# STM32-ROMI_Rev_A_3_OLED_Sensor.net
KiCad netlist of a schematic drawn in Altium Designer
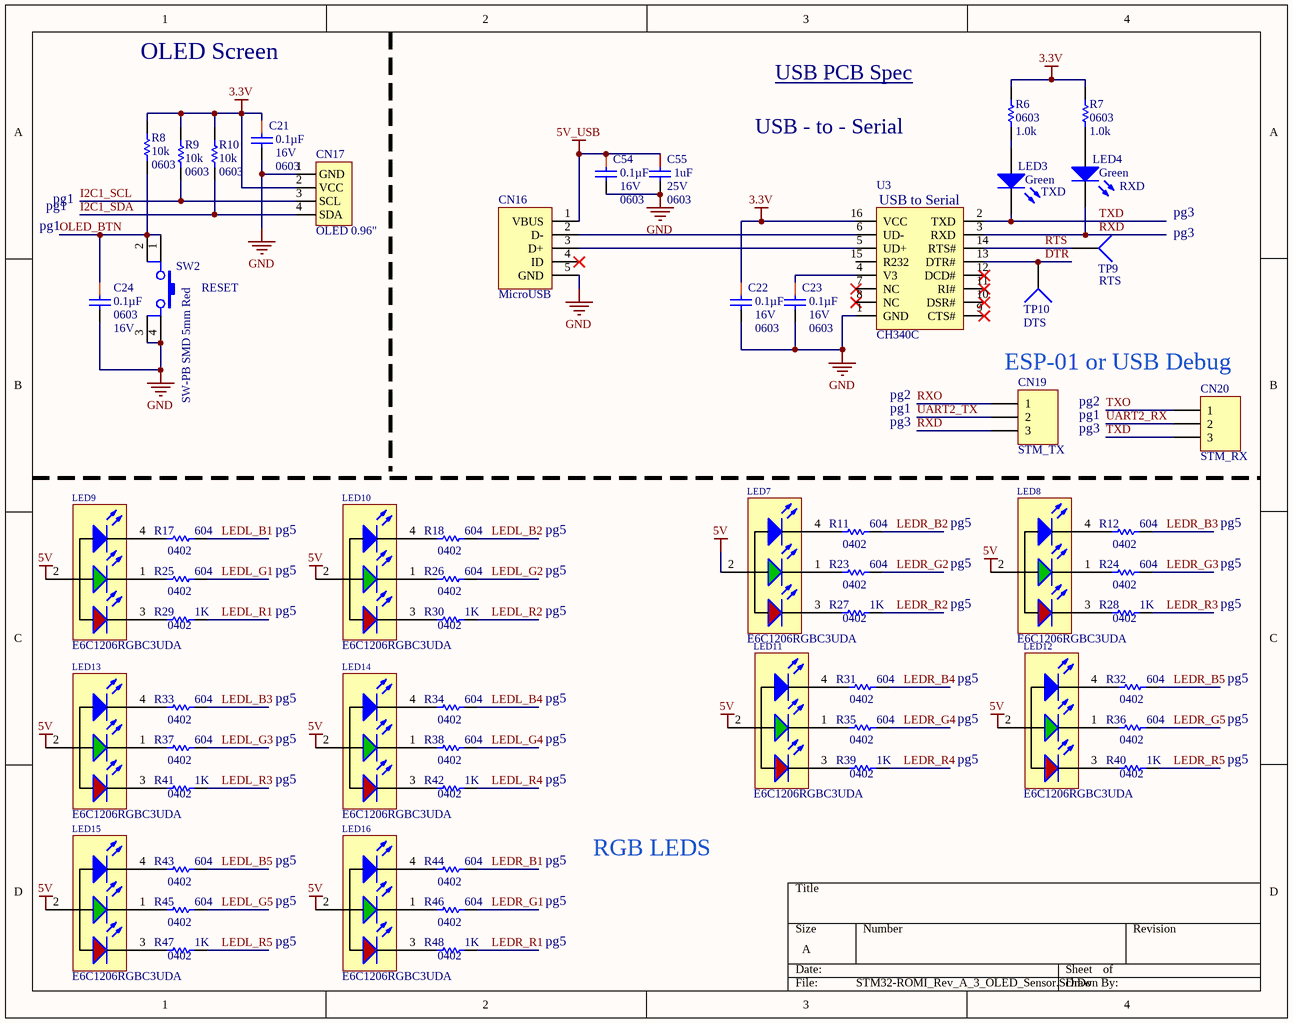
[diagram p0: STM32-ROMI_Rev_A_3_OLED_Sensor.SchDoc]

(export (version "E")
  (design (tool "Eeschema 10.0.6"))
  (components
    (comp (ref "C21")
      (value "0.1uF")
      (footprint "CAPC0603(1608)_L")
      (description "0.1uF 0603 16V")
      (fields
        (field (name "MANUFACTURER") "Kemet")
        (field (name "MANUFACTURER PART NUMBER") "C0603C104K4RACTU")
        (field (name "CAPACITANCE") "0.1µF")
        (field (name "PACKAGE / CASE") "0603")
        (field (name "VOLTAGE - RATED") "16V")
      )
      (libsource (lib "Kyle-Passive") (part "CAP CER 0.1UF 16V 10% X7R 0603"))
    )
    (comp (ref "C22")
      (value "0.1uF")
      (footprint "CAPC0603(1608)_L")
      (description "0.1uF 0603 16V")
      (fields
        (field (name "MANUFACTURER") "Kemet")
        (field (name "MANUFACTURER PART NUMBER") "C0603C104K4RACTU")
        (field (name "CAPACITANCE") "0.1µF")
        (field (name "PACKAGE / CASE") "0603")
        (field (name "VOLTAGE - RATED") "16V")
      )
      (libsource (lib "Kyle-Passive") (part "CAP CER 0.1UF 16V 10% X7R 0603"))
    )
    (comp (ref "C23")
      (value "0.1uF")
      (footprint "CAPC0603(1608)_L")
      (description "0.1uF 0603 16V")
      (fields
        (field (name "MANUFACTURER") "Kemet")
        (field (name "MANUFACTURER PART NUMBER") "C0603C104K4RACTU")
        (field (name "CAPACITANCE") "0.1µF")
        (field (name "PACKAGE / CASE") "0603")
        (field (name "VOLTAGE - RATED") "16V")
      )
      (libsource (lib "Kyle-Passive") (part "CAP CER 0.1UF 16V 10% X7R 0603"))
    )
    (comp (ref "C24")
      (value "0.1uF")
      (footprint "CAPC0603(1608)_L")
      (description "0.1uF 0603 16V")
      (fields
        (field (name "MANUFACTURER") "Kemet")
        (field (name "MANUFACTURER PART NUMBER") "C0603C104K4RACTU")
        (field (name "CAPACITANCE") "0.1µF")
        (field (name "PACKAGE / CASE") "0603")
        (field (name "VOLTAGE - RATED") "16V")
      )
      (libsource (lib "JLCPCB_Passives") (part "CAP CER 0.1UF 16V 10% X7R 0603"))
    )
    (comp (ref "C54")
      (value "0.1uF")
      (footprint "CAPC0603(1608)_L")
      (description "0.1uF 0603 16V")
      (fields
        (field (name "MANUFACTURER") "Kemet")
        (field (name "MANUFACTURER PART NUMBER") "C0603C104K4RACTU")
        (field (name "CAPACITANCE") "0.1µF")
        (field (name "PACKAGE / CASE") "0603")
        (field (name "VOLTAGE - RATED") "16V")
      )
      (libsource (lib "Kyle-Passive") (part "CAP CER 0.1UF 16V 10% X7R 0603"))
    )
    (comp (ref "C55")
      (value "1uF")
      (footprint "CAPC0603(1608)_N")
      (description "1uF 0603 25V")
      (fields
        (field (name "MANUFACTURER") "TDK Corporation")
        (field (name "MANUFACTURER PART NUMBER") "CGA3E1X7R1E105K080AC")
        (field (name "VOLTAGE - RATED") "25V")
        (field (name "PACKAGE / CASE") "0603")
      )
      (libsource (lib "OLogic-Passive") (part "CAP CER 1UF 25V 10% X7R 0603"))
    )
    (comp (ref "CN16")
      (value "MicroUSB")
      (footprint "10118194-0001LF")
      (description "Amphenol FCI CONN USB MICRO B RECPT SMT R/A")
      (fields
        (field (name "MANUFACTURER") "Amphenol FCI")
        (field (name "MANUFACTURER PART NUMBER") "10118194-0001LF")
      )
      (libsource (lib "OLogic-Connectors") (part "10118194-0001LF"))
    )
    (comp (ref "CN17")
      (value "OLED 0.96\"")
      (footprint "OLED_0.96_I2C")
      (description "SSD1306 I2C OLED 0.96\"")
      (libsource (lib "Kyle_Lib_04-20-19") (part "OLED_0.96_I2C"))
    )
    (comp (ref "CN19")
      (value "STM_TX")
      (footprint "HDR1X3")
      (description "Header, 3-Pin")
      (fields
        (field (name "MANUFACTURER") "Sullins Connector Solutions")
        (field (name "MANUFACTURER PART NUMBER") "PRPC003SAAN-RC")
      )
      (libsource (lib "Kyle-Connectors") (part "Header 3"))
    )
    (comp (ref "CN20")
      (value "STM_RX")
      (footprint "HDR1X3")
      (description "Header, 3-Pin")
      (fields
        (field (name "MANUFACTURER") "Sullins Connector Solutions")
        (field (name "MANUFACTURER PART NUMBER") "PRPC003SAAN-RC")
      )
      (libsource (lib "Kyle-Connectors") (part "Header 3"))
    )
    (comp (ref "LED3")
      (value "TXD")
      (footprint "SM-LED-0603")
      (description "LED GREEN CLEAR THIN 0603 SMD")
      (fields
        (field (name "MANUFACTURER") "Lite-On Inc")
        (field (name "MANUFACTURER PART NUMBER") "LTST-C191KGKT")
        (field (name "COLOR") "Green")
      )
      (libsource (lib "Kyle-Diode-Opto-LED") (part "LTST-C191KGKT"))
    )
    (comp (ref "LED4")
      (value "RXD")
      (footprint "SM-LED-0603")
      (description "LED GREEN CLEAR THIN 0603 SMD")
      (fields
        (field (name "MANUFACTURER") "Lite-On Inc")
        (field (name "MANUFACTURER PART NUMBER") "LTST-C191KGKT")
        (field (name "COLOR") "Green")
      )
      (libsource (lib "Kyle-Diode-Opto-LED") (part "LTST-C191KGKT"))
    )
    (comp (ref "LED7")
      (value "E6C1206RGBC3UDA")
      (footprint "E6C1206RGBC3UDA")
      (description "RGB 620NMRED, 520NMGREEN, 465NMBLUE SMD,")
      (libsource (lib "JLCPCB-LED-Diodes") (part "RGB LED"))
    )
    (comp (ref "LED8")
      (value "E6C1206RGBC3UDA")
      (footprint "E6C1206RGBC3UDA")
      (description "RGB 620NMRED, 520NMGREEN, 465NMBLUE SMD,")
      (libsource (lib "JLCPCB-LED-Diodes") (part "RGB LED"))
    )
    (comp (ref "LED9")
      (value "E6C1206RGBC3UDA")
      (footprint "E6C1206RGBC3UDA")
      (description "RGB 620NMRED, 520NMGREEN, 465NMBLUE SMD,")
      (libsource (lib "JLCPCB-LED-Diodes") (part "RGB LED"))
    )
    (comp (ref "LED10")
      (value "E6C1206RGBC3UDA")
      (footprint "E6C1206RGBC3UDA")
      (description "RGB 620NMRED, 520NMGREEN, 465NMBLUE SMD,")
      (libsource (lib "JLCPCB-LED-Diodes") (part "RGB LED"))
    )
    (comp (ref "LED11")
      (value "E6C1206RGBC3UDA")
      (footprint "E6C1206RGBC3UDA")
      (description "RGB 620NMRED, 520NMGREEN, 465NMBLUE SMD,")
      (libsource (lib "JLCPCB-LED-Diodes") (part "RGB LED"))
    )
    (comp (ref "LED12")
      (value "E6C1206RGBC3UDA")
      (footprint "E6C1206RGBC3UDA")
      (description "RGB 620NMRED, 520NMGREEN, 465NMBLUE SMD,")
      (libsource (lib "JLCPCB-LED-Diodes") (part "RGB LED"))
    )
    (comp (ref "LED13")
      (value "E6C1206RGBC3UDA")
      (footprint "E6C1206RGBC3UDA")
      (description "RGB 620NMRED, 520NMGREEN, 465NMBLUE SMD,")
      (libsource (lib "JLCPCB-LED-Diodes") (part "RGB LED"))
    )
    (comp (ref "LED14")
      (value "E6C1206RGBC3UDA")
      (footprint "E6C1206RGBC3UDA")
      (description "RGB 620NMRED, 520NMGREEN, 465NMBLUE SMD,")
      (libsource (lib "JLCPCB-LED-Diodes") (part "RGB LED"))
    )
    (comp (ref "LED15")
      (value "E6C1206RGBC3UDA")
      (footprint "E6C1206RGBC3UDA")
      (description "RGB 620NMRED, 520NMGREEN, 465NMBLUE SMD,")
      (libsource (lib "JLCPCB-LED-Diodes") (part "RGB LED"))
    )
    (comp (ref "LED16")
      (value "E6C1206RGBC3UDA")
      (footprint "E6C1206RGBC3UDA")
      (description "RGB 620NMRED, 520NMGREEN, 465NMBLUE SMD,")
      (libsource (lib "JLCPCB-LED-Diodes") (part "RGB LED"))
    )
    (comp (ref "R6")
      (value "1.0K")
      (footprint "RESC0603(1608)_N")
      (description "1.0K 0603")
      (fields
        (field (name "MANUFACTURER") "Stackpole Electronics Inc.")
        (field (name "MANUFACTURER PART NUMBER") "RMCF0603FT1K00")
        (field (name "PACKAGE / CASE") "0603")
        (field (name "RESISTANCE (OHMS)") "1.0k")
      )
      (libsource (lib "Kyle-Passive") (part "RES 1K OHM 1% 1/10W 0603"))
    )
    (comp (ref "R7")
      (value "1.0K")
      (footprint "RESC0603(1608)_N")
      (description "1.0K 0603")
      (fields
        (field (name "MANUFACTURER") "Stackpole Electronics Inc.")
        (field (name "MANUFACTURER PART NUMBER") "RMCF0603FT1K00")
        (field (name "PACKAGE / CASE") "0603")
        (field (name "RESISTANCE (OHMS)") "1.0k")
      )
      (libsource (lib "Kyle-Passive") (part "RES 1K OHM 1% 1/10W 0603"))
    )
    (comp (ref "R8")
      (value "10K 1%")
      (footprint "RESC0603(1608)_L")
      (description "10K 0603")
      (fields
        (field (name "MANUFACTURER") "Panasonic Electronic Components")
        (field (name "MANUFACTURER PART NUMBER") "ERJ-3EKF1002V")
        (field (name "RESISTANCE (OHMS)") "10k")
        (field (name "PACKAGE / CASE") "0603")
      )
      (libsource (lib "Kyle-Passive") (part "RES 10K OHM 1/10W 1% 0603 SMD"))
    )
    (comp (ref "R9")
      (value "10K 1%")
      (footprint "RESC0603(1608)_L")
      (description "10K 0603")
      (fields
        (field (name "MANUFACTURER") "Panasonic Electronic Components")
        (field (name "MANUFACTURER PART NUMBER") "ERJ-3EKF1002V")
        (field (name "RESISTANCE (OHMS)") "10k")
        (field (name "PACKAGE / CASE") "0603")
      )
      (libsource (lib "Kyle-Passive") (part "RES 10K OHM 1/10W 1% 0603 SMD"))
    )
    (comp (ref "R10")
      (value "10K 1%")
      (footprint "RESC0603(1608)_L")
      (description "10K 0603")
      (fields
        (field (name "MANUFACTURER") "Panasonic Electronic Components")
        (field (name "MANUFACTURER PART NUMBER") "ERJ-3EKF1002V")
        (field (name "RESISTANCE (OHMS)") "10k")
        (field (name "PACKAGE / CASE") "0603")
      )
      (libsource (lib "Kyle-Passive") (part "RES 10K OHM 1/10W 1% 0603 SMD"))
    )
    (comp (ref "R11")
      (value "604")
      (footprint "RESC0402(1005)_L")
      (description "604 0402")
      (fields
        (field (name "MANUFACTURER") "Panasonic Electronic Components")
        (field (name "MANUFACTURER PART NUMBER") "ERA-2AEB6040X")
        (field (name "SUPPLIER DEVICE PACKAGE") "0402")
      )
      (libsource (lib "OLogic-Passive") (part "RES 604 OHM 1% 1/10W 0402"))
    )
    (comp (ref "R12")
      (value "604")
      (footprint "RESC0402(1005)_L")
      (description "604 0402")
      (fields
        (field (name "MANUFACTURER") "Panasonic Electronic Components")
        (field (name "MANUFACTURER PART NUMBER") "ERA-2AEB6040X")
        (field (name "SUPPLIER DEVICE PACKAGE") "0402")
      )
      (libsource (lib "OLogic-Passive") (part "RES 604 OHM 1% 1/10W 0402"))
    )
    (comp (ref "R17")
      (value "604")
      (footprint "RESC0402(1005)_L")
      (description "604 0402")
      (fields
        (field (name "MANUFACTURER") "Panasonic Electronic Components")
        (field (name "MANUFACTURER PART NUMBER") "ERA-2AEB6040X")
        (field (name "SUPPLIER DEVICE PACKAGE") "0402")
      )
      (libsource (lib "OLogic-Passive") (part "RES 604 OHM 1% 1/10W 0402"))
    )
    (comp (ref "R18")
      (value "604")
      (footprint "RESC0402(1005)_L")
      (description "604 0402")
      (fields
        (field (name "MANUFACTURER") "Panasonic Electronic Components")
        (field (name "MANUFACTURER PART NUMBER") "ERA-2AEB6040X")
        (field (name "SUPPLIER DEVICE PACKAGE") "0402")
      )
      (libsource (lib "OLogic-Passive") (part "RES 604 OHM 1% 1/10W 0402"))
    )
    (comp (ref "R23")
      (value "604")
      (footprint "RESC0402(1005)_L")
      (description "604 0402")
      (fields
        (field (name "MANUFACTURER") "Panasonic Electronic Components")
        (field (name "MANUFACTURER PART NUMBER") "ERA-2AEB6040X")
        (field (name "SUPPLIER DEVICE PACKAGE") "0402")
      )
      (libsource (lib "OLogic-Passive") (part "RES 604 OHM 1% 1/10W 0402"))
    )
    (comp (ref "R24")
      (value "604")
      (footprint "RESC0402(1005)_L")
      (description "604 0402")
      (fields
        (field (name "MANUFACTURER") "Panasonic Electronic Components")
        (field (name "MANUFACTURER PART NUMBER") "ERA-2AEB6040X")
        (field (name "SUPPLIER DEVICE PACKAGE") "0402")
      )
      (libsource (lib "OLogic-Passive") (part "RES 604 OHM 1% 1/10W 0402"))
    )
    (comp (ref "R25")
      (value "604")
      (footprint "RESC0402(1005)_L")
      (description "604 0402")
      (fields
        (field (name "MANUFACTURER") "Panasonic Electronic Components")
        (field (name "MANUFACTURER PART NUMBER") "ERA-2AEB6040X")
        (field (name "SUPPLIER DEVICE PACKAGE") "0402")
      )
      (libsource (lib "OLogic-Passive") (part "RES 604 OHM 1% 1/10W 0402"))
    )
    (comp (ref "R26")
      (value "604")
      (footprint "RESC0402(1005)_L")
      (description "604 0402")
      (fields
        (field (name "MANUFACTURER") "Panasonic Electronic Components")
        (field (name "MANUFACTURER PART NUMBER") "ERA-2AEB6040X")
        (field (name "SUPPLIER DEVICE PACKAGE") "0402")
      )
      (libsource (lib "OLogic-Passive") (part "RES 604 OHM 1% 1/10W 0402"))
    )
    (comp (ref "R27")
      (value "1K")
      (footprint "RESC0402(1005)_L")
      (description "1K 0402")
      (fields
        (field (name "MANUFACTURER") "Yageo")
        (field (name "MANUFACTURER PART NUMBER") "RC0402FR-071KL")
        (field (name "CASE CODE (IMPERIAL)") "0402")
        (field (name "RESISTANCE") "1K")
      )
      (libsource (lib "OLogic-Passive") (part "RES 1K OHM 1% 1/16W 0402"))
    )
    (comp (ref "R28")
      (value "1K")
      (footprint "RESC0402(1005)_L")
      (description "1K 0402")
      (fields
        (field (name "MANUFACTURER") "Yageo")
        (field (name "MANUFACTURER PART NUMBER") "RC0402FR-071KL")
        (field (name "CASE CODE (IMPERIAL)") "0402")
        (field (name "RESISTANCE") "1K")
      )
      (libsource (lib "OLogic-Passive") (part "RES 1K OHM 1% 1/16W 0402"))
    )
    (comp (ref "R29")
      (value "1K")
      (footprint "RESC0402(1005)_L")
      (description "1K 0402")
      (fields
        (field (name "MANUFACTURER") "Yageo")
        (field (name "MANUFACTURER PART NUMBER") "RC0402FR-071KL")
        (field (name "CASE CODE (IMPERIAL)") "0402")
        (field (name "RESISTANCE") "1K")
      )
      (libsource (lib "OLogic-Passive") (part "RES 1K OHM 1% 1/16W 0402"))
    )
    (comp (ref "R30")
      (value "1K")
      (footprint "RESC0402(1005)_L")
      (description "1K 0402")
      (fields
        (field (name "MANUFACTURER") "Yageo")
        (field (name "MANUFACTURER PART NUMBER") "RC0402FR-071KL")
        (field (name "CASE CODE (IMPERIAL)") "0402")
        (field (name "RESISTANCE") "1K")
      )
      (libsource (lib "OLogic-Passive") (part "RES 1K OHM 1% 1/16W 0402"))
    )
    (comp (ref "R31")
      (value "604")
      (footprint "RESC0402(1005)_L")
      (description "604 0402")
      (fields
        (field (name "MANUFACTURER") "Panasonic Electronic Components")
        (field (name "MANUFACTURER PART NUMBER") "ERA-2AEB6040X")
        (field (name "SUPPLIER DEVICE PACKAGE") "0402")
      )
      (libsource (lib "OLogic-Passive") (part "RES 604 OHM 1% 1/10W 0402"))
    )
    (comp (ref "R32")
      (value "604")
      (footprint "RESC0402(1005)_L")
      (description "604 0402")
      (fields
        (field (name "MANUFACTURER") "Panasonic Electronic Components")
        (field (name "MANUFACTURER PART NUMBER") "ERA-2AEB6040X")
        (field (name "SUPPLIER DEVICE PACKAGE") "0402")
      )
      (libsource (lib "OLogic-Passive") (part "RES 604 OHM 1% 1/10W 0402"))
    )
    (comp (ref "R33")
      (value "604")
      (footprint "RESC0402(1005)_L")
      (description "604 0402")
      (fields
        (field (name "MANUFACTURER") "Panasonic Electronic Components")
        (field (name "MANUFACTURER PART NUMBER") "ERA-2AEB6040X")
        (field (name "SUPPLIER DEVICE PACKAGE") "0402")
      )
      (libsource (lib "OLogic-Passive") (part "RES 604 OHM 1% 1/10W 0402"))
    )
    (comp (ref "R34")
      (value "604")
      (footprint "RESC0402(1005)_L")
      (description "604 0402")
      (fields
        (field (name "MANUFACTURER") "Panasonic Electronic Components")
        (field (name "MANUFACTURER PART NUMBER") "ERA-2AEB6040X")
        (field (name "SUPPLIER DEVICE PACKAGE") "0402")
      )
      (libsource (lib "OLogic-Passive") (part "RES 604 OHM 1% 1/10W 0402"))
    )
    (comp (ref "R35")
      (value "604")
      (footprint "RESC0402(1005)_L")
      (description "604 0402")
      (fields
        (field (name "MANUFACTURER") "Panasonic Electronic Components")
        (field (name "MANUFACTURER PART NUMBER") "ERA-2AEB6040X")
        (field (name "SUPPLIER DEVICE PACKAGE") "0402")
      )
      (libsource (lib "OLogic-Passive") (part "RES 604 OHM 1% 1/10W 0402"))
    )
    (comp (ref "R36")
      (value "604")
      (footprint "RESC0402(1005)_L")
      (description "604 0402")
      (fields
        (field (name "MANUFACTURER") "Panasonic Electronic Components")
        (field (name "MANUFACTURER PART NUMBER") "ERA-2AEB6040X")
        (field (name "SUPPLIER DEVICE PACKAGE") "0402")
      )
      (libsource (lib "OLogic-Passive") (part "RES 604 OHM 1% 1/10W 0402"))
    )
    (comp (ref "R37")
      (value "604")
      (footprint "RESC0402(1005)_L")
      (description "604 0402")
      (fields
        (field (name "MANUFACTURER") "Panasonic Electronic Components")
        (field (name "MANUFACTURER PART NUMBER") "ERA-2AEB6040X")
        (field (name "SUPPLIER DEVICE PACKAGE") "0402")
      )
      (libsource (lib "OLogic-Passive") (part "RES 604 OHM 1% 1/10W 0402"))
    )
    (comp (ref "R38")
      (value "604")
      (footprint "RESC0402(1005)_L")
      (description "604 0402")
      (fields
        (field (name "MANUFACTURER") "Panasonic Electronic Components")
        (field (name "MANUFACTURER PART NUMBER") "ERA-2AEB6040X")
        (field (name "SUPPLIER DEVICE PACKAGE") "0402")
      )
      (libsource (lib "OLogic-Passive") (part "RES 604 OHM 1% 1/10W 0402"))
    )
    (comp (ref "R39")
      (value "1K")
      (footprint "RESC0402(1005)_L")
      (description "1K 0402")
      (fields
        (field (name "MANUFACTURER") "Yageo")
        (field (name "MANUFACTURER PART NUMBER") "RC0402FR-071KL")
        (field (name "CASE CODE (IMPERIAL)") "0402")
        (field (name "RESISTANCE") "1K")
      )
      (libsource (lib "OLogic-Passive") (part "RES 1K OHM 1% 1/16W 0402"))
    )
    (comp (ref "R40")
      (value "1K")
      (footprint "RESC0402(1005)_L")
      (description "1K 0402")
      (fields
        (field (name "MANUFACTURER") "Yageo")
        (field (name "MANUFACTURER PART NUMBER") "RC0402FR-071KL")
        (field (name "CASE CODE (IMPERIAL)") "0402")
        (field (name "RESISTANCE") "1K")
      )
      (libsource (lib "OLogic-Passive") (part "RES 1K OHM 1% 1/16W 0402"))
    )
    (comp (ref "R41")
      (value "1K")
      (footprint "RESC0402(1005)_L")
      (description "1K 0402")
      (fields
        (field (name "MANUFACTURER") "Yageo")
        (field (name "MANUFACTURER PART NUMBER") "RC0402FR-071KL")
        (field (name "CASE CODE (IMPERIAL)") "0402")
        (field (name "RESISTANCE") "1K")
      )
      (libsource (lib "OLogic-Passive") (part "RES 1K OHM 1% 1/16W 0402"))
    )
    (comp (ref "R42")
      (value "1K")
      (footprint "RESC0402(1005)_L")
      (description "1K 0402")
      (fields
        (field (name "MANUFACTURER") "Yageo")
        (field (name "MANUFACTURER PART NUMBER") "RC0402FR-071KL")
        (field (name "CASE CODE (IMPERIAL)") "0402")
        (field (name "RESISTANCE") "1K")
      )
      (libsource (lib "OLogic-Passive") (part "RES 1K OHM 1% 1/16W 0402"))
    )
    (comp (ref "R43")
      (value "604")
      (footprint "RESC0402(1005)_L")
      (description "604 0402")
      (fields
        (field (name "MANUFACTURER") "Panasonic Electronic Components")
        (field (name "MANUFACTURER PART NUMBER") "ERA-2AEB6040X")
        (field (name "SUPPLIER DEVICE PACKAGE") "0402")
      )
      (libsource (lib "OLogic-Passive") (part "RES 604 OHM 1% 1/10W 0402"))
    )
    (comp (ref "R44")
      (value "604")
      (footprint "RESC0402(1005)_L")
      (description "604 0402")
      (fields
        (field (name "MANUFACTURER") "Panasonic Electronic Components")
        (field (name "MANUFACTURER PART NUMBER") "ERA-2AEB6040X")
        (field (name "SUPPLIER DEVICE PACKAGE") "0402")
      )
      (libsource (lib "OLogic-Passive") (part "RES 604 OHM 1% 1/10W 0402"))
    )
    (comp (ref "R45")
      (value "604")
      (footprint "RESC0402(1005)_L")
      (description "604 0402")
      (fields
        (field (name "MANUFACTURER") "Panasonic Electronic Components")
        (field (name "MANUFACTURER PART NUMBER") "ERA-2AEB6040X")
        (field (name "SUPPLIER DEVICE PACKAGE") "0402")
      )
      (libsource (lib "OLogic-Passive") (part "RES 604 OHM 1% 1/10W 0402"))
    )
    (comp (ref "R46")
      (value "604")
      (footprint "RESC0402(1005)_L")
      (description "604 0402")
      (fields
        (field (name "MANUFACTURER") "Panasonic Electronic Components")
        (field (name "MANUFACTURER PART NUMBER") "ERA-2AEB6040X")
        (field (name "SUPPLIER DEVICE PACKAGE") "0402")
      )
      (libsource (lib "OLogic-Passive") (part "RES 604 OHM 1% 1/10W 0402"))
    )
    (comp (ref "R47")
      (value "1K")
      (footprint "RESC0402(1005)_L")
      (description "1K 0402")
      (fields
        (field (name "MANUFACTURER") "Yageo")
        (field (name "MANUFACTURER PART NUMBER") "RC0402FR-071KL")
        (field (name "CASE CODE (IMPERIAL)") "0402")
        (field (name "RESISTANCE") "1K")
      )
      (libsource (lib "OLogic-Passive") (part "RES 1K OHM 1% 1/16W 0402"))
    )
    (comp (ref "R48")
      (value "1K")
      (footprint "RESC0402(1005)_L")
      (description "1K 0402")
      (fields
        (field (name "MANUFACTURER") "Yageo")
        (field (name "MANUFACTURER PART NUMBER") "RC0402FR-071KL")
        (field (name "CASE CODE (IMPERIAL)") "0402")
        (field (name "RESISTANCE") "1K")
      )
      (libsource (lib "OLogic-Passive") (part "RES 1K OHM 1% 1/16W 0402"))
    )
    (comp (ref "SW2")
      (value "RESET")
      (footprint "SW TACT Red 6mm x 6mm")
      (description "SWITCH TACTILE SPST-NO 0.05A 12V")
      (fields
        (field (name "MANUFACTURER") "C&K Components")
        (field (name "MANUFACTURER PART NUMBER") "PTS645SK50SMTR92 LFS")
        (field (name "TEXT") "SW-PB SMD 5mm Red")
        (field (name "PUBLISHER") "Altium Limited")
      )
      (libsource (lib "OLogic-Switches") (part "SW-PB SMD 5mm Red"))
    )
    (comp (ref "TP9")
      (value "RTS")
      (footprint "TestPoint-SM")
      (description "Test Point")
      (libsource (lib "OLogic-Misc") (part "TestPoint"))
    )
    (comp (ref "TP10")
      (value "DTS")
      (footprint "TestPoint-SM")
      (description "Test Point")
      (libsource (lib "OLogic-Misc") (part "TestPoint"))
    )
    (comp (ref "U3")
      (value "CH340C")
      (footprint "SOP-16")
      (description "USB to Serial UART")
      (libsource (lib "Kyle_Lib_04-20-19") (part "CH340C"))
    )
  )
  (nets
    (net (code "1") (name "/DTR") (class "Default")
      (node (ref "TP10") (pin "1") (pinfunction "1_1") (pintype "passive"))
      (node (ref "U3") (pin "13") (pinfunction "DTR#_13") (pintype "power_in"))
    )
    (net (code "2") (name "/I2C1_SCL") (class "Default")
      (node (ref "CN17") (pin "3") (pinfunction "SCL_3") (pintype "passive"))
      (node (ref "R9") (pin "1") (pinfunction "1_1") (pintype "passive"))
    )
    (net (code "3") (name "/I2C1_SDA") (class "Default")
      (node (ref "CN17") (pin "4") (pinfunction "SDA_4") (pintype "passive"))
      (node (ref "R10") (pin "1") (pinfunction "1_1") (pintype "passive"))
    )
    (net (code "4") (name "/LEDL_B1") (class "Default")
      (node (ref "R17") (pin "1") (pinfunction "1_1") (pintype "passive"))
    )
    (net (code "5") (name "/LEDL_B2") (class "Default")
      (node (ref "R18") (pin "1") (pinfunction "1_1") (pintype "passive"))
    )
    (net (code "6") (name "/LEDL_B3") (class "Default")
      (node (ref "R33") (pin "1") (pinfunction "1_1") (pintype "passive"))
    )
    (net (code "7") (name "/LEDL_B4") (class "Default")
      (node (ref "R34") (pin "1") (pinfunction "1_1") (pintype "passive"))
    )
    (net (code "8") (name "/LEDL_B5") (class "Default")
      (node (ref "R43") (pin "1") (pinfunction "1_1") (pintype "passive"))
    )
    (net (code "9") (name "/LEDL_G1") (class "Default")
      (node (ref "R25") (pin "1") (pinfunction "1_1") (pintype "passive"))
    )
    (net (code "10") (name "/LEDL_G2") (class "Default")
      (node (ref "R26") (pin "1") (pinfunction "1_1") (pintype "passive"))
    )
    (net (code "11") (name "/LEDL_G3") (class "Default")
      (node (ref "R37") (pin "1") (pinfunction "1_1") (pintype "passive"))
    )
    (net (code "12") (name "/LEDL_G4") (class "Default")
      (node (ref "R38") (pin "1") (pinfunction "1_1") (pintype "passive"))
    )
    (net (code "13") (name "/LEDL_G5") (class "Default")
      (node (ref "R45") (pin "1") (pinfunction "1_1") (pintype "passive"))
    )
    (net (code "14") (name "/LEDL_R1") (class "Default")
      (node (ref "R29") (pin "1") (pinfunction "1_1") (pintype "passive"))
    )
    (net (code "15") (name "/LEDL_R2") (class "Default")
      (node (ref "R30") (pin "1") (pinfunction "1_1") (pintype "passive"))
    )
    (net (code "16") (name "/LEDL_R3") (class "Default")
      (node (ref "R41") (pin "1") (pinfunction "1_1") (pintype "passive"))
    )
    (net (code "17") (name "/LEDL_R4") (class "Default")
      (node (ref "R42") (pin "1") (pinfunction "1_1") (pintype "passive"))
    )
    (net (code "18") (name "/LEDL_R5") (class "Default")
      (node (ref "R47") (pin "1") (pinfunction "1_1") (pintype "passive"))
    )
    (net (code "19") (name "/LEDR_B1") (class "Default")
      (node (ref "R44") (pin "1") (pinfunction "1_1") (pintype "passive"))
    )
    (net (code "20") (name "/LEDR_B2") (class "Default")
      (node (ref "R11") (pin "1") (pinfunction "1_1") (pintype "passive"))
    )
    (net (code "21") (name "/LEDR_B3") (class "Default")
      (node (ref "R12") (pin "1") (pinfunction "1_1") (pintype "passive"))
    )
    (net (code "22") (name "/LEDR_B4") (class "Default")
      (node (ref "R31") (pin "1") (pinfunction "1_1") (pintype "passive"))
    )
    (net (code "23") (name "/LEDR_B5") (class "Default")
      (node (ref "R32") (pin "1") (pinfunction "1_1") (pintype "passive"))
    )
    (net (code "24") (name "/LEDR_G1") (class "Default")
      (node (ref "R46") (pin "1") (pinfunction "1_1") (pintype "passive"))
    )
    (net (code "25") (name "/LEDR_G2") (class "Default")
      (node (ref "R23") (pin "1") (pinfunction "1_1") (pintype "passive"))
    )
    (net (code "26") (name "/LEDR_G3") (class "Default")
      (node (ref "R24") (pin "1") (pinfunction "1_1") (pintype "passive"))
    )
    (net (code "27") (name "/LEDR_G4") (class "Default")
      (node (ref "R35") (pin "1") (pinfunction "1_1") (pintype "passive"))
    )
    (net (code "28") (name "/LEDR_G5") (class "Default")
      (node (ref "R36") (pin "1") (pinfunction "1_1") (pintype "passive"))
    )
    (net (code "29") (name "/LEDR_R1") (class "Default")
      (node (ref "R48") (pin "1") (pinfunction "1_1") (pintype "passive"))
    )
    (net (code "30") (name "/LEDR_R2") (class "Default")
      (node (ref "R27") (pin "1") (pinfunction "1_1") (pintype "passive"))
    )
    (net (code "31") (name "/LEDR_R3") (class "Default")
      (node (ref "R28") (pin "1") (pinfunction "1_1") (pintype "passive"))
    )
    (net (code "32") (name "/LEDR_R4") (class "Default")
      (node (ref "R39") (pin "1") (pinfunction "1_1") (pintype "passive"))
    )
    (net (code "33") (name "/LEDR_R5") (class "Default")
      (node (ref "R40") (pin "1") (pinfunction "1_1") (pintype "passive"))
    )
    (net (code "34") (name "/OLED_BTN") (class "Default")
      (node (ref "C24") (pin "1") (pinfunction "1_1") (pintype "passive"))
      (node (ref "R8") (pin "1") (pinfunction "1_1") (pintype "passive"))
      (node (ref "SW2") (pin "1") (pinfunction "1_1") (pintype "passive"))
      (node (ref "SW2") (pin "2") (pinfunction "2_2") (pintype "passive"))
    )
    (net (code "35") (name "/RTS") (class "Default")
      (node (ref "TP9") (pin "1") (pinfunction "1_1") (pintype "passive"))
      (node (ref "U3") (pin "14") (pinfunction "RTS#_14") (pintype "power_in"))
    )
    (net (code "36") (name "/RXD") (class "Default")
      (node (ref "CN19") (pin "3") (pinfunction "3_3") (pintype "passive"))
      (node (ref "LED4") (pin "2") (pinfunction "2_2") (pintype "passive"))
      (node (ref "U3") (pin "3") (pinfunction "RXD_3") (pintype "power_in"))
    )
    (net (code "37") (name "/RXO") (class "Default")
      (node (ref "CN19") (pin "1") (pinfunction "1_1") (pintype "passive"))
    )
    (net (code "38") (name "/TXD") (class "Default")
      (node (ref "CN20") (pin "3") (pinfunction "3_3") (pintype "passive"))
      (node (ref "LED3") (pin "2") (pinfunction "2_2") (pintype "passive"))
      (node (ref "U3") (pin "2") (pinfunction "TXD_2") (pintype "power_in"))
    )
    (net (code "39") (name "/TXO") (class "Default")
      (node (ref "CN20") (pin "1") (pinfunction "1_1") (pintype "passive"))
    )
    (net (code "40") (name "/UART2_RX") (class "Default")
      (node (ref "CN20") (pin "2") (pinfunction "2_2") (pintype "passive"))
    )
    (net (code "41") (name "/UART2_TX") (class "Default")
      (node (ref "CN19") (pin "2") (pinfunction "2_2") (pintype "passive"))
    )
    (net (code "42") (name "3.3V") (class "Default")
      (node (ref "C21") (pin "1") (pinfunction "1_1") (pintype "passive"))
      (node (ref "C22") (pin "1") (pinfunction "1_1") (pintype "passive"))
      (node (ref "CN17") (pin "2") (pinfunction "VCC_2") (pintype "passive"))
      (node (ref "R10") (pin "2") (pinfunction "2_2") (pintype "passive"))
      (node (ref "R6") (pin "2") (pinfunction "2_2") (pintype "passive"))
      (node (ref "R7") (pin "2") (pinfunction "2_2") (pintype "passive"))
      (node (ref "R8") (pin "2") (pinfunction "2_2") (pintype "passive"))
      (node (ref "R9") (pin "2") (pinfunction "2_2") (pintype "passive"))
      (node (ref "U3") (pin "16") (pinfunction "VCC_16") (pintype "power_in"))
    )
    (net (code "43") (name "5V") (class "Default")
      (node (ref "LED10") (pin "2") (pinfunction "+_2") (pintype "passive"))
      (node (ref "LED11") (pin "2") (pinfunction "+_2") (pintype "passive"))
      (node (ref "LED12") (pin "2") (pinfunction "+_2") (pintype "passive"))
      (node (ref "LED13") (pin "2") (pinfunction "+_2") (pintype "passive"))
      (node (ref "LED14") (pin "2") (pinfunction "+_2") (pintype "passive"))
      (node (ref "LED15") (pin "2") (pinfunction "+_2") (pintype "passive"))
      (node (ref "LED16") (pin "2") (pinfunction "+_2") (pintype "passive"))
      (node (ref "LED7") (pin "2") (pinfunction "+_2") (pintype "passive"))
      (node (ref "LED8") (pin "2") (pinfunction "+_2") (pintype "passive"))
      (node (ref "LED9") (pin "2") (pinfunction "+_2") (pintype "passive"))
    )
    (net (code "44") (name "5V_USB") (class "Default")
      (node (ref "C54") (pin "1") (pinfunction "1_1") (pintype "passive"))
      (node (ref "C55") (pin "1") (pinfunction "1_1") (pintype "passive"))
      (node (ref "CN16") (pin "1") (pinfunction "VBUS_1") (pintype "power_in"))
    )
    (net (code "45") (name "GND") (class "Default")
      (node (ref "C21") (pin "2") (pinfunction "2_2") (pintype "passive"))
      (node (ref "C22") (pin "2") (pinfunction "2_2") (pintype "passive"))
      (node (ref "C23") (pin "2") (pinfunction "2_2") (pintype "passive"))
      (node (ref "C24") (pin "2") (pinfunction "2_2") (pintype "passive"))
      (node (ref "C54") (pin "2") (pinfunction "2_2") (pintype "passive"))
      (node (ref "C55") (pin "2") (pinfunction "2_2") (pintype "passive"))
      (node (ref "CN16") (pin "5") (pinfunction "GND_5") (pintype "power_in"))
      (node (ref "CN17") (pin "1") (pinfunction "GND_1") (pintype "passive"))
      (node (ref "SW2") (pin "3") (pinfunction "3_3") (pintype "passive"))
      (node (ref "SW2") (pin "4") (pinfunction "4_4") (pintype "passive"))
      (node (ref "U3") (pin "1") (pinfunction "GND_1") (pintype "power_in"))
    )
    (net (code "46") (name "Net-(CN16-D+)") (class "Default")
      (node (ref "CN16") (pin "3") (pinfunction "D+_3") (pintype "passive"))
      (node (ref "U3") (pin "5") (pinfunction "UD+_5") (pintype "power_in"))
    )
    (net (code "47") (name "Net-(CN16-D-)") (class "Default")
      (node (ref "CN16") (pin "2") (pinfunction "D-_2") (pintype "passive"))
      (node (ref "U3") (pin "6") (pinfunction "UD-_6") (pintype "power_in"))
    )
    (net (code "48") (name "Net-(LED3-Pad1)") (class "Default")
      (node (ref "LED3") (pin "1") (pinfunction "1_1") (pintype "passive"))
      (node (ref "R6") (pin "1") (pinfunction "1_1") (pintype "passive"))
    )
    (net (code "49") (name "Net-(LED4-Pad1)") (class "Default")
      (node (ref "LED4") (pin "1") (pinfunction "1_1") (pintype "passive"))
      (node (ref "R7") (pin "1") (pinfunction "1_1") (pintype "passive"))
    )
    (net (code "50") (name "Net-(LED7-A)") (class "Default")
      (node (ref "LED7") (pin "3") (pinfunction "A_3") (pintype "passive"))
      (node (ref "R27") (pin "2") (pinfunction "2_2") (pintype "passive"))
    )
    (net (code "51") (name "Net-(LED7-B)") (class "Default")
      (node (ref "LED7") (pin "1") (pinfunction "B_1") (pintype "passive"))
      (node (ref "R23") (pin "2") (pinfunction "2_2") (pintype "passive"))
    )
    (net (code "52") (name "Net-(LED7-R)") (class "Default")
      (node (ref "LED7") (pin "4") (pinfunction "R_4") (pintype "passive"))
      (node (ref "R11") (pin "2") (pinfunction "2_2") (pintype "passive"))
    )
    (net (code "53") (name "Net-(LED8-A)") (class "Default")
      (node (ref "LED8") (pin "3") (pinfunction "A_3") (pintype "passive"))
      (node (ref "R28") (pin "2") (pinfunction "2_2") (pintype "passive"))
    )
    (net (code "54") (name "Net-(LED8-B)") (class "Default")
      (node (ref "LED8") (pin "1") (pinfunction "B_1") (pintype "passive"))
      (node (ref "R24") (pin "2") (pinfunction "2_2") (pintype "passive"))
    )
    (net (code "55") (name "Net-(LED8-R)") (class "Default")
      (node (ref "LED8") (pin "4") (pinfunction "R_4") (pintype "passive"))
      (node (ref "R12") (pin "2") (pinfunction "2_2") (pintype "passive"))
    )
    (net (code "56") (name "Net-(LED9-A)") (class "Default")
      (node (ref "LED9") (pin "3") (pinfunction "A_3") (pintype "passive"))
      (node (ref "R29") (pin "2") (pinfunction "2_2") (pintype "passive"))
    )
    (net (code "57") (name "Net-(LED9-B)") (class "Default")
      (node (ref "LED9") (pin "1") (pinfunction "B_1") (pintype "passive"))
      (node (ref "R25") (pin "2") (pinfunction "2_2") (pintype "passive"))
    )
    (net (code "58") (name "Net-(LED9-R)") (class "Default")
      (node (ref "LED9") (pin "4") (pinfunction "R_4") (pintype "passive"))
      (node (ref "R17") (pin "2") (pinfunction "2_2") (pintype "passive"))
    )
    (net (code "59") (name "Net-(LED10-A)") (class "Default")
      (node (ref "LED10") (pin "3") (pinfunction "A_3") (pintype "passive"))
      (node (ref "R30") (pin "2") (pinfunction "2_2") (pintype "passive"))
    )
    (net (code "60") (name "Net-(LED10-B)") (class "Default")
      (node (ref "LED10") (pin "1") (pinfunction "B_1") (pintype "passive"))
      (node (ref "R26") (pin "2") (pinfunction "2_2") (pintype "passive"))
    )
    (net (code "61") (name "Net-(LED10-R)") (class "Default")
      (node (ref "LED10") (pin "4") (pinfunction "R_4") (pintype "passive"))
      (node (ref "R18") (pin "2") (pinfunction "2_2") (pintype "passive"))
    )
    (net (code "62") (name "Net-(LED11-A)") (class "Default")
      (node (ref "LED11") (pin "3") (pinfunction "A_3") (pintype "passive"))
      (node (ref "R39") (pin "2") (pinfunction "2_2") (pintype "passive"))
    )
    (net (code "63") (name "Net-(LED11-B)") (class "Default")
      (node (ref "LED11") (pin "1") (pinfunction "B_1") (pintype "passive"))
      (node (ref "R35") (pin "2") (pinfunction "2_2") (pintype "passive"))
    )
    (net (code "64") (name "Net-(LED11-R)") (class "Default")
      (node (ref "LED11") (pin "4") (pinfunction "R_4") (pintype "passive"))
      (node (ref "R31") (pin "2") (pinfunction "2_2") (pintype "passive"))
    )
    (net (code "65") (name "Net-(LED12-A)") (class "Default")
      (node (ref "LED12") (pin "3") (pinfunction "A_3") (pintype "passive"))
      (node (ref "R40") (pin "2") (pinfunction "2_2") (pintype "passive"))
    )
    (net (code "66") (name "Net-(LED12-B)") (class "Default")
      (node (ref "LED12") (pin "1") (pinfunction "B_1") (pintype "passive"))
      (node (ref "R36") (pin "2") (pinfunction "2_2") (pintype "passive"))
    )
    (net (code "67") (name "Net-(LED12-R)") (class "Default")
      (node (ref "LED12") (pin "4") (pinfunction "R_4") (pintype "passive"))
      (node (ref "R32") (pin "2") (pinfunction "2_2") (pintype "passive"))
    )
    (net (code "68") (name "Net-(LED13-A)") (class "Default")
      (node (ref "LED13") (pin "3") (pinfunction "A_3") (pintype "passive"))
      (node (ref "R41") (pin "2") (pinfunction "2_2") (pintype "passive"))
    )
    (net (code "69") (name "Net-(LED13-B)") (class "Default")
      (node (ref "LED13") (pin "1") (pinfunction "B_1") (pintype "passive"))
      (node (ref "R37") (pin "2") (pinfunction "2_2") (pintype "passive"))
    )
    (net (code "70") (name "Net-(LED13-R)") (class "Default")
      (node (ref "LED13") (pin "4") (pinfunction "R_4") (pintype "passive"))
      (node (ref "R33") (pin "2") (pinfunction "2_2") (pintype "passive"))
    )
    (net (code "71") (name "Net-(LED14-A)") (class "Default")
      (node (ref "LED14") (pin "3") (pinfunction "A_3") (pintype "passive"))
      (node (ref "R42") (pin "2") (pinfunction "2_2") (pintype "passive"))
    )
    (net (code "72") (name "Net-(LED14-B)") (class "Default")
      (node (ref "LED14") (pin "1") (pinfunction "B_1") (pintype "passive"))
      (node (ref "R38") (pin "2") (pinfunction "2_2") (pintype "passive"))
    )
    (net (code "73") (name "Net-(LED14-R)") (class "Default")
      (node (ref "LED14") (pin "4") (pinfunction "R_4") (pintype "passive"))
      (node (ref "R34") (pin "2") (pinfunction "2_2") (pintype "passive"))
    )
    (net (code "74") (name "Net-(LED15-A)") (class "Default")
      (node (ref "LED15") (pin "3") (pinfunction "A_3") (pintype "passive"))
      (node (ref "R47") (pin "2") (pinfunction "2_2") (pintype "passive"))
    )
    (net (code "75") (name "Net-(LED15-B)") (class "Default")
      (node (ref "LED15") (pin "1") (pinfunction "B_1") (pintype "passive"))
      (node (ref "R45") (pin "2") (pinfunction "2_2") (pintype "passive"))
    )
    (net (code "76") (name "Net-(LED15-R)") (class "Default")
      (node (ref "LED15") (pin "4") (pinfunction "R_4") (pintype "passive"))
      (node (ref "R43") (pin "2") (pinfunction "2_2") (pintype "passive"))
    )
    (net (code "77") (name "Net-(LED16-A)") (class "Default")
      (node (ref "LED16") (pin "3") (pinfunction "A_3") (pintype "passive"))
      (node (ref "R48") (pin "2") (pinfunction "2_2") (pintype "passive"))
    )
    (net (code "78") (name "Net-(LED16-B)") (class "Default")
      (node (ref "LED16") (pin "1") (pinfunction "B_1") (pintype "passive"))
      (node (ref "R46") (pin "2") (pinfunction "2_2") (pintype "passive"))
    )
    (net (code "79") (name "Net-(LED16-R)") (class "Default")
      (node (ref "LED16") (pin "4") (pinfunction "R_4") (pintype "passive"))
      (node (ref "R44") (pin "2") (pinfunction "2_2") (pintype "passive"))
    )
    (net (code "80") (name "Net-(U3-V3)") (class "Default")
      (node (ref "C23") (pin "1") (pinfunction "1_1") (pintype "passive"))
      (node (ref "U3") (pin "4") (pinfunction "V3_4") (pintype "power_in"))
    )
    (net (code "81") (name "unconnected-(CN16-ID-Pad4)") (class "Default")
      (node (ref "CN16") (pin "4") (pinfunction "ID_4") (pintype "passive+no_connect"))
    )
    (net (code "82") (name "unconnected-(U3-CTS#-Pad9)") (class "Default")
      (node (ref "U3") (pin "9") (pinfunction "CTS#_9") (pintype "power_in+no_connect"))
    )
    (net (code "83") (name "unconnected-(U3-DCD#-Pad12)") (class "Default")
      (node (ref "U3") (pin "12") (pinfunction "DCD#_12") (pintype "power_in+no_connect"))
    )
    (net (code "84") (name "unconnected-(U3-DSR#-Pad10)") (class "Default")
      (node (ref "U3") (pin "10") (pinfunction "DSR#_10") (pintype "power_in+no_connect"))
    )
    (net (code "85") (name "unconnected-(U3-NC-Pad7)") (class "Default")
      (node (ref "U3") (pin "7") (pinfunction "NC_7") (pintype "power_in+no_connect"))
    )
    (net (code "86") (name "unconnected-(U3-NC-Pad8)") (class "Default")
      (node (ref "U3") (pin "8") (pinfunction "NC_8") (pintype "power_in+no_connect"))
    )
    (net (code "87") (name "unconnected-(U3-R232-Pad15)") (class "Default")
      (node (ref "U3") (pin "15") (pinfunction "R232_15") (pintype "power_in"))
    )
    (net (code "88") (name "unconnected-(U3-RI#-Pad11)") (class "Default")
      (node (ref "U3") (pin "11") (pinfunction "RI#_11") (pintype "power_in+no_connect"))
    )
  )
)
